# Kello_Nixie_PWR.net
KiCad netlist of a schematic drawn in Altium Designer
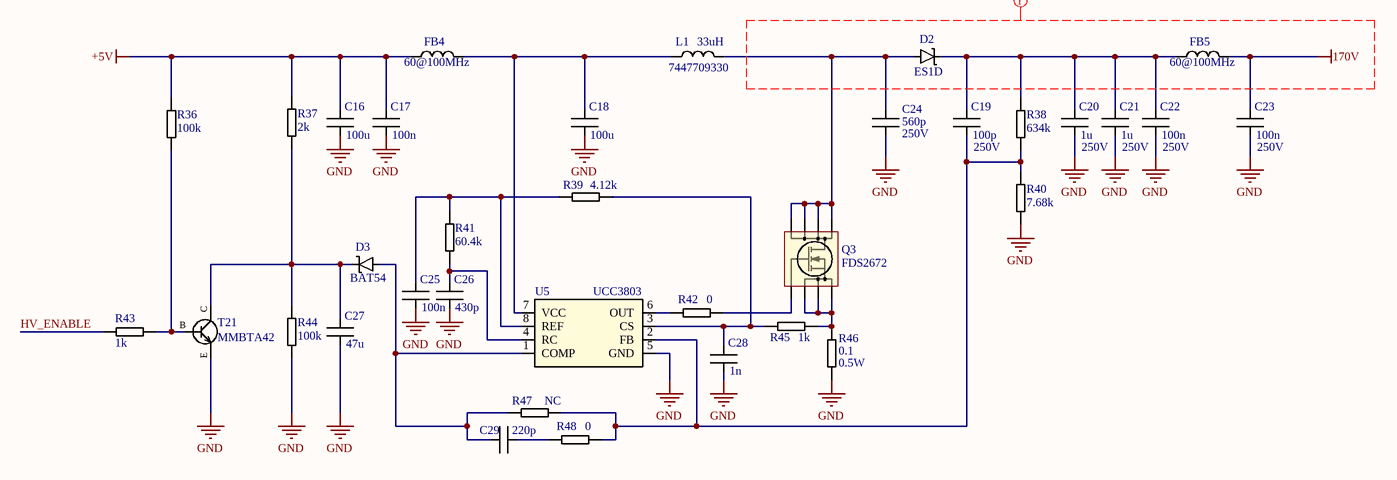
[diagram p0: Kello_Nixie_PWR.SchDoc]

(export (version "E")
  (design (tool "Eeschema 10.0.6"))
  (components
    (comp (ref "C16")
      (value "100u")
      (footprint "CAPC4532N")
      (description "Capacitor")
      (fields (field (name "TOLERANCE") "20%"))
      (libsource (lib "RLC") (part "Capacitor"))
    )
    (comp (ref "C17")
      (value "100n")
      (footprint "CAPC1608N")
      (description "Capacitor")
      (fields (field (name "TOLERANCE") "-20/+80%"))
      (libsource (lib "RLC") (part "Capacitor"))
    )
    (comp (ref "C18")
      (value "100u")
      (footprint "CAPC4532N")
      (description "Capacitor")
      (fields (field (name "TOLERANCE") "20%"))
      (libsource (lib "RLC") (part "Capacitor"))
    )
    (comp (ref "C19")
      (value "100p")
      (footprint "CAPC1608N")
      (description "Capacitor")
      (fields (field (name "TOLERANCE") "5%") (field (name "MAXVOLTAGE") "250V"))
      (libsource (lib "RLC") (part "Capacitor"))
    )
    (comp (ref "C20")
      (value "1u")
      (footprint "CAPC4532N")
      (description "Capacitor")
      (fields (field (name "TOLERANCE") "10%") (field (name "MAXVOLTAGE") "250V"))
      (libsource (lib "RLC") (part "Capacitor"))
    )
    (comp (ref "C21")
      (value "1u")
      (footprint "CAPC4532N")
      (description "Capacitor")
      (fields (field (name "TOLERANCE") "10%") (field (name "MAXVOLTAGE") "250V"))
      (libsource (lib "RLC") (part "Capacitor"))
    )
    (comp (ref "C22")
      (value "100n")
      (footprint "CAPC3216N")
      (description "Capacitor")
      (fields (field (name "TOLERANCE") "10%") (field (name "MAXVOLTAGE") "250V"))
      (libsource (lib "RLC") (part "Capacitor"))
    )
    (comp (ref "C23")
      (value "100n")
      (footprint "CAPC3216N")
      (description "Capacitor")
      (fields (field (name "TOLERANCE") "10%") (field (name "MAXVOLTAGE") "250V"))
      (libsource (lib "RLC") (part "Capacitor"))
    )
    (comp (ref "C24")
      (value "560p")
      (footprint "CAPC1608N")
      (description "Capacitor")
      (fields (field (name "TOLERANCE") "5%") (field (name "MAXVOLTAGE") "250V"))
      (libsource (lib "RLC") (part "Capacitor"))
    )
    (comp (ref "C25")
      (value "100n")
      (footprint "CAPC1608N")
      (description "Capacitor")
      (fields (field (name "TOLERANCE") "-20/+80%"))
      (libsource (lib "RLC") (part "Capacitor"))
    )
    (comp (ref "C26")
      (value "430p")
      (footprint "CAPC1608N")
      (description "Capacitor")
      (fields (field (name "TOLERANCE") "5%"))
      (libsource (lib "RLC") (part "Capacitor"))
    )
    (comp (ref "C27")
      (value "47u")
      (footprint "CAPC3225N")
      (description "Capacitor")
      (fields (field (name "TOLERANCE") "20%"))
      (libsource (lib "RLC") (part "Capacitor"))
    )
    (comp (ref "C28")
      (value "1n")
      (footprint "CAPC1608N")
      (description "Capacitor")
      (fields (field (name "TOLERANCE") "10%"))
      (libsource (lib "RLC") (part "Capacitor"))
    )
    (comp (ref "C29")
      (value "220p")
      (footprint "CAPC1608N")
      (description "Capacitor")
      (fields (field (name "TOLERANCE") "10%"))
      (libsource (lib "RLC") (part "Capacitor"))
    )
    (comp (ref "D2")
      (value "ES1D")
      (footprint "SUB-SMA")
      (description "Dioda: prostownicza; SMD; 200V; 1A; 15ns; 1,47W; SMA; Ifsm:30A")
      (fields (field (name "MANUFACTURER") "ON SEMICONDUCTOR"))
      (libsource (lib "Diodes") (part "SS19L"))
    )
    (comp (ref "D3")
      (value "BAT54")
      (footprint "SOD-523F")
      (description "Fairchild BAT54XV2, Schottky, 200mA, 30V")
      (fields (field (name "MANUFACTURER") "Fairchild") (field (name "MANUFACTURER PART NUMBER") "BAT54XV2"))
      (libsource (lib "Diodes") (part "BAT54XV2"))
    )
    (comp (ref "FB4")
      (value "60@100MHz")
      (footprint "INDC1608N")
      (description "Ferrite Bead")
      (libsource (lib "RLC") (part "Inductor"))
    )
    (comp (ref "FB5")
      (value "60@100MHz")
      (footprint "INDC1608N")
      (description "Ferrite Bead")
      (libsource (lib "RLC") (part "Inductor"))
    )
    (comp (ref "L1")
      (value "7447709330")
      (footprint "WE_PD")
      (description "Cewka zasilająca (SMD), 33 µH, 4.2 A, Osłonięte, 5.5 A, Seria WE-PD, 12mm x 12mm x 10mm")
      (fields (field (name "TOLERANCE") "20%") (field (name "ALTIUM_VALUE") "33uH"))
      (libsource (lib "WE_Inductors") (part "7447709330"))
    )
    (comp (ref "Q3")
      (value "FDS2672")
      (footprint "SO8_N")
      (description "Tranzystor: N-MOSFET; unipolarny; 200V; 3,9A; 2,5W; SO8; UltraFET®")
      (libsource (lib "On_Semiconductor_Transistors") (part "FDS2672"))
    )
    (comp (ref "R36")
      (value "100k")
      (footprint "RESC1608N")
      (description "Resistor")
      (fields (field (name "TOLERANCE") "1%") (field (name "POWER") "0.1W"))
      (libsource (lib "RLC") (part "Resistor"))
    )
    (comp (ref "R37")
      (value "2k")
      (footprint "RESC1608N")
      (description "Resistor")
      (fields (field (name "TOLERANCE") "1%") (field (name "POWER") "0.1W"))
      (libsource (lib "RLC") (part "Resistor"))
    )
    (comp (ref "R38")
      (value "634k")
      (footprint "RESC3216N")
      (description "Resistor")
      (fields (field (name "TOLERANCE") "1%") (field (name "POWER") "0.25W"))
      (libsource (lib "RLC") (part "Resistor"))
    )
    (comp (ref "R39")
      (value "4.12k")
      (footprint "RESC1608N")
      (description "Resistor")
      (fields (field (name "TOLERANCE") "1%") (field (name "POWER") "0.1W"))
      (libsource (lib "RLC") (part "Resistor"))
    )
    (comp (ref "R40")
      (value "7.68k")
      (footprint "RESC3216N")
      (description "Resistor")
      (fields (field (name "TOLERANCE") "1%") (field (name "POWER") "0.25W"))
      (libsource (lib "RLC") (part "Resistor"))
    )
    (comp (ref "R41")
      (value "60.4k")
      (footprint "RESC1608N")
      (description "Resistor")
      (fields (field (name "TOLERANCE") "1%") (field (name "POWER") "0.1W"))
      (libsource (lib "RLC") (part "Resistor"))
    )
    (comp (ref "R42")
      (value "0")
      (footprint "RESC1608N")
      (description "Resistor")
      (fields (field (name "TOLERANCE") "1%") (field (name "POWER") "0.1W"))
      (libsource (lib "RLC") (part "Resistor"))
    )
    (comp (ref "R43")
      (value "1k")
      (footprint "RESC1608N")
      (description "Resistor")
      (fields (field (name "TOLERANCE") "1%") (field (name "POWER") "0.1W"))
      (libsource (lib "RLC") (part "Resistor"))
    )
    (comp (ref "R44")
      (value "100k")
      (footprint "RESC1608N")
      (description "Resistor")
      (fields (field (name "TOLERANCE") "1%") (field (name "POWER") "0.1W"))
      (libsource (lib "RLC") (part "Resistor"))
    )
    (comp (ref "R45")
      (value "1k")
      (footprint "RESC1608N")
      (description "Resistor")
      (fields (field (name "TOLERANCE") "1%") (field (name "POWER") "0.1W"))
      (libsource (lib "RLC") (part "Resistor"))
    )
    (comp (ref "R46")
      (value "0.1")
      (footprint "RESC3216N")
      (description "Resistor")
      (fields (field (name "TOLERANCE") "1%") (field (name "POWER") "0.5W"))
      (libsource (lib "RLC") (part "Resistor"))
    )
    (comp (ref "R47")
      (value "NC")
      (footprint "RESC1608N")
      (description "Resistor")
      (fields (field (name "TOLERANCE") "1%") (field (name "POWER") "0.1W"))
      (libsource (lib "RLC") (part "Resistor"))
    )
    (comp (ref "R48")
      (value "0")
      (footprint "RESC1608N")
      (description "Resistor")
      (fields (field (name "TOLERANCE") "1%") (field (name "POWER") "0.1W"))
      (libsource (lib "RLC") (part "Resistor"))
    )
    (comp (ref "T21")
      (value "MMBTA42")
      (footprint "SOT23-3N")
      (description "NPN Transistor")
      (libsource (lib "Transistors") (part "2N3707"))
    )
    (comp (ref "U5")
      (value "UCC3803")
      (footprint "SOIC8+PAD (SOIC127P600X170_HS-9N)")
      (description "Kontroler PWM current mode, zasilanie 12V-3.6V, 1 MHz, wyjście 1V/1A, SOIC-8")
      (libsource (lib "TexasInstruments-Power") (part "UCC3803"))
    )
  )
  (nets
    (net (code "1") (name "+5V") (class "Default")
      (node (ref "C16") (pin "2") (pinfunction "2_2") (pintype "passive"))
      (node (ref "C17") (pin "2") (pinfunction "2_2") (pintype "passive"))
      (node (ref "FB4") (pin "1") (pinfunction "1_1") (pintype "passive"))
      (node (ref "R36") (pin "1") (pinfunction "1_1") (pintype "passive"))
      (node (ref "R37") (pin "1") (pinfunction "1_1") (pintype "passive"))
    )
    (net (code "2") (name "/HV_ENABLE") (class "Default")
      (node (ref "R43") (pin "1") (pinfunction "1_1") (pintype "passive"))
    )
    (net (code "3") (name "170V") (class "Default")
      (node (ref "C23") (pin "2") (pinfunction "2_2") (pintype "passive"))
      (node (ref "FB5") (pin "2") (pinfunction "2_2") (pintype "passive"))
    )
    (net (code "4") (name "GND") (class "Default")
      (node (ref "C16") (pin "1") (pinfunction "1_1") (pintype "passive"))
      (node (ref "C17") (pin "1") (pinfunction "1_1") (pintype "passive"))
      (node (ref "C18") (pin "1") (pinfunction "1_1") (pintype "passive"))
      (node (ref "C20") (pin "1") (pinfunction "1_1") (pintype "passive"))
      (node (ref "C21") (pin "1") (pinfunction "1_1") (pintype "passive"))
      (node (ref "C22") (pin "1") (pinfunction "1_1") (pintype "passive"))
      (node (ref "C23") (pin "1") (pinfunction "1_1") (pintype "passive"))
      (node (ref "C24") (pin "1") (pinfunction "1_1") (pintype "passive"))
      (node (ref "C25") (pin "1") (pinfunction "1_1") (pintype "passive"))
      (node (ref "C26") (pin "1") (pinfunction "1_1") (pintype "passive"))
      (node (ref "C27") (pin "1") (pinfunction "1_1") (pintype "passive"))
      (node (ref "C28") (pin "1") (pinfunction "1_1") (pintype "passive"))
      (node (ref "R40") (pin "2") (pinfunction "2_2") (pintype "passive"))
      (node (ref "R44") (pin "2") (pinfunction "2_2") (pintype "passive"))
      (node (ref "R46") (pin "2") (pinfunction "2_2") (pintype "passive"))
      (node (ref "T21") (pin "E") (pinfunction "E_E") (pintype "passive"))
      (node (ref "U5") (pin "5") (pinfunction "GND_5") (pintype "passive"))
    )
    (net (code "5") (name "Net-(C19-Pad2)") (class "Default")
      (node (ref "C19") (pin "2") (pinfunction "2_2") (pintype "passive"))
      (node (ref "C20") (pin "2") (pinfunction "2_2") (pintype "passive"))
      (node (ref "C21") (pin "2") (pinfunction "2_2") (pintype "passive"))
      (node (ref "C22") (pin "2") (pinfunction "2_2") (pintype "passive"))
      (node (ref "D2") (pin "K") (pinfunction "K_K") (pintype "passive"))
      (node (ref "FB5") (pin "1") (pinfunction "1_1") (pintype "passive"))
      (node (ref "R38") (pin "1") (pinfunction "1_1") (pintype "passive"))
    )
    (net (code "6") (name "Net-(C24-Pad2)") (class "Default")
      (node (ref "C24") (pin "2") (pinfunction "2_2") (pintype "passive"))
      (node (ref "D2") (pin "A") (pinfunction "A_A") (pintype "passive"))
      (node (ref "L1") (pin "2") (pinfunction "2_2") (pintype "passive"))
      (node (ref "Q3") (pin "5") (pinfunction "D_5") (pintype "passive"))
      (node (ref "Q3") (pin "6") (pinfunction "D_6") (pintype "passive"))
      (node (ref "Q3") (pin "7") (pinfunction "D_7") (pintype "passive"))
      (node (ref "Q3") (pin "8") (pinfunction "D_8") (pintype "passive"))
    )
    (net (code "7") (name "Net-(C27-Pad2)") (class "Default")
      (node (ref "C27") (pin "2") (pinfunction "2_2") (pintype "passive"))
      (node (ref "D3") (pin "K") (pinfunction "K_K") (pintype "passive"))
      (node (ref "R37") (pin "2") (pinfunction "2_2") (pintype "passive"))
      (node (ref "R44") (pin "1") (pinfunction "1_1") (pintype "passive"))
      (node (ref "T21") (pin "C") (pinfunction "C_C") (pintype "passive"))
    )
    (net (code "8") (name "Net-(C29-Pad1)") (class "Default")
      (node (ref "C29") (pin "1") (pinfunction "1_1") (pintype "passive"))
      (node (ref "R48") (pin "1") (pinfunction "1_1") (pintype "passive"))
    )
    (net (code "9") (name "Net-(Q3-G)") (class "Default")
      (node (ref "Q3") (pin "4") (pinfunction "G_4") (pintype "passive"))
      (node (ref "R42") (pin "2") (pinfunction "2_2") (pintype "passive"))
    )
    (net (code "10") (name "Net-(Q3-S-Pad1)") (class "Default")
      (node (ref "Q3") (pin "1") (pinfunction "S_1") (pintype "passive"))
      (node (ref "Q3") (pin "2") (pinfunction "S_2") (pintype "passive"))
      (node (ref "Q3") (pin "3") (pinfunction "S_3") (pintype "passive"))
      (node (ref "R45") (pin "2") (pinfunction "2_2") (pintype "passive"))
      (node (ref "R46") (pin "1") (pinfunction "1_1") (pintype "passive"))
    )
    (net (code "11") (name "Net-(R36-Pad2)") (class "Default")
      (node (ref "R36") (pin "2") (pinfunction "2_2") (pintype "passive"))
      (node (ref "R43") (pin "2") (pinfunction "2_2") (pintype "passive"))
      (node (ref "T21") (pin "B") (pinfunction "B_B") (pintype "passive"))
    )
    (net (code "12") (name "Net-(U5-COMP)") (class "Default")
      (node (ref "C29") (pin "2") (pinfunction "2_2") (pintype "passive"))
      (node (ref "D3") (pin "A") (pinfunction "A_A") (pintype "passive"))
      (node (ref "R47") (pin "1") (pinfunction "1_1") (pintype "passive"))
      (node (ref "U5") (pin "1") (pinfunction "COMP_1") (pintype "passive"))
    )
    (net (code "13") (name "Net-(U5-CS)") (class "Default")
      (node (ref "C28") (pin "2") (pinfunction "2_2") (pintype "passive"))
      (node (ref "R39") (pin "2") (pinfunction "2_2") (pintype "passive"))
      (node (ref "R45") (pin "1") (pinfunction "1_1") (pintype "passive"))
      (node (ref "U5") (pin "3") (pinfunction "CS_3") (pintype "passive"))
    )
    (net (code "14") (name "Net-(U5-FB)") (class "Default")
      (node (ref "C19") (pin "1") (pinfunction "1_1") (pintype "passive"))
      (node (ref "R38") (pin "2") (pinfunction "2_2") (pintype "passive"))
      (node (ref "R40") (pin "1") (pinfunction "1_1") (pintype "passive"))
      (node (ref "R47") (pin "2") (pinfunction "2_2") (pintype "passive"))
      (node (ref "R48") (pin "2") (pinfunction "2_2") (pintype "passive"))
      (node (ref "U5") (pin "2") (pinfunction "FB_2") (pintype "passive"))
    )
    (net (code "15") (name "Net-(U5-OUT)") (class "Default")
      (node (ref "R42") (pin "1") (pinfunction "1_1") (pintype "passive"))
      (node (ref "U5") (pin "6") (pinfunction "OUT_6") (pintype "passive"))
    )
    (net (code "16") (name "Net-(U5-RC)") (class "Default")
      (node (ref "C26") (pin "2") (pinfunction "2_2") (pintype "passive"))
      (node (ref "R41") (pin "2") (pinfunction "2_2") (pintype "passive"))
      (node (ref "U5") (pin "4") (pinfunction "RC_4") (pintype "passive"))
    )
    (net (code "17") (name "Net-(U5-REF)") (class "Default")
      (node (ref "C25") (pin "2") (pinfunction "2_2") (pintype "passive"))
      (node (ref "R39") (pin "1") (pinfunction "1_1") (pintype "passive"))
      (node (ref "R41") (pin "1") (pinfunction "1_1") (pintype "passive"))
      (node (ref "U5") (pin "8") (pinfunction "REF_8") (pintype "passive"))
    )
    (net (code "18") (name "Net-(U5-VCC)") (class "Default")
      (node (ref "C18") (pin "2") (pinfunction "2_2") (pintype "passive"))
      (node (ref "FB4") (pin "2") (pinfunction "2_2") (pintype "passive"))
      (node (ref "L1") (pin "1") (pinfunction "1_1") (pintype "passive"))
      (node (ref "U5") (pin "7") (pinfunction "VCC_7") (pintype "passive"))
    )
  )
)
